# LQFP100_Breakout.net
KiCad netlist of a schematic drawn in EAGLE
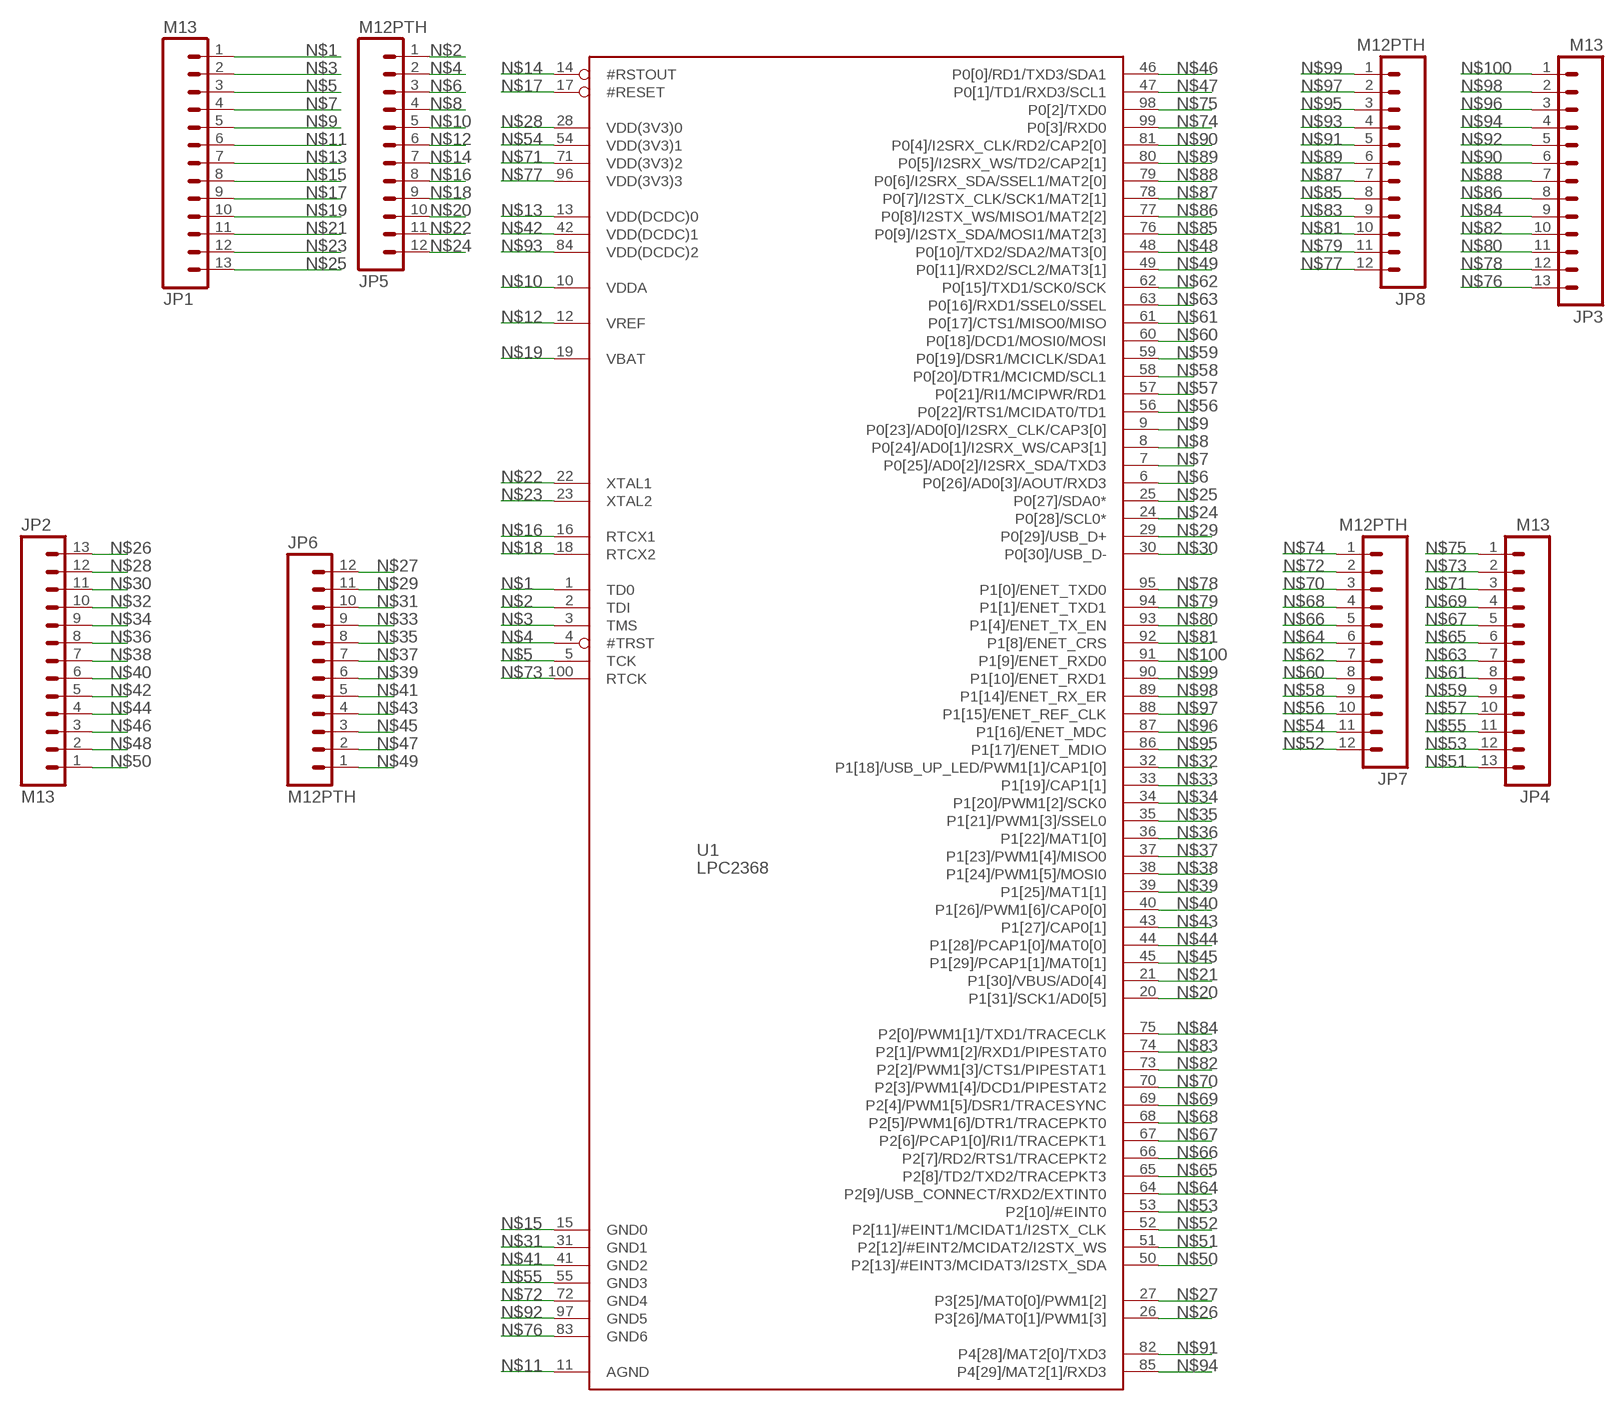
[diagram p0: schematic, sheet 1]

(export (version "E")
  (design (tool "Eeschema 10.0.6"))
  (components
    (comp (ref "JP1")
      (value "M13")
      (footprint "eagle-import:1X13")
      (libsource (lib "eagle-import") (part "M13"))
    )
    (comp (ref "JP2")
      (value "M13")
      (footprint "eagle-import:1X13")
      (libsource (lib "eagle-import") (part "M13"))
    )
    (comp (ref "JP3")
      (value "M13")
      (footprint "eagle-import:1X13")
      (libsource (lib "eagle-import") (part "M13"))
    )
    (comp (ref "JP4")
      (value "M13")
      (footprint "eagle-import:1X13")
      (libsource (lib "eagle-import") (part "M13"))
    )
    (comp (ref "JP5")
      (value "M12PTH")
      (footprint "eagle-import:1X12")
      (libsource (lib "eagle-import") (part "M12PTH"))
    )
    (comp (ref "JP6")
      (value "M12PTH")
      (footprint "eagle-import:1X12")
      (libsource (lib "eagle-import") (part "M12PTH"))
    )
    (comp (ref "JP7")
      (value "M12PTH")
      (footprint "eagle-import:1X12")
      (libsource (lib "eagle-import") (part "M12PTH"))
    )
    (comp (ref "JP8")
      (value "M12PTH")
      (footprint "eagle-import:1X12")
      (libsource (lib "eagle-import") (part "M12PTH"))
    )
    (comp (ref "U1")
      (value "LPC2368")
      (footprint "eagle-import:LQFP100")
      (libsource (lib "eagle-import") (part "LPC2368"))
    )
  )
  (nets
    (net (code "1") (name "/N$1") (class "Default")
      (node (ref "JP1") (pin "1") (pinfunction "1_1") (pintype "passive"))
      (node (ref "U1") (pin "1") (pinfunction "TD0_1") (pintype "bidirectional"))
    )
    (net (code "2") (name "/N$2") (class "Default")
      (node (ref "JP5") (pin "1") (pinfunction "1_1") (pintype "passive"))
      (node (ref "U1") (pin "2") (pinfunction "TDI_2") (pintype "bidirectional"))
    )
    (net (code "3") (name "/N$3") (class "Default")
      (node (ref "JP1") (pin "2") (pinfunction "2_2") (pintype "passive"))
      (node (ref "U1") (pin "3") (pinfunction "TMS_3") (pintype "bidirectional"))
    )
    (net (code "4") (name "/N$4") (class "Default")
      (node (ref "JP5") (pin "2") (pinfunction "2_2") (pintype "passive"))
      (node (ref "U1") (pin "4") (pinfunction "#TRST_4") (pintype "bidirectional"))
    )
    (net (code "5") (name "/N$5") (class "Default")
      (node (ref "JP1") (pin "3") (pinfunction "3_3") (pintype "passive"))
      (node (ref "U1") (pin "5") (pinfunction "TCK_5") (pintype "bidirectional"))
    )
    (net (code "6") (name "/N$6") (class "Default")
      (node (ref "JP5") (pin "3") (pinfunction "3_3") (pintype "passive"))
      (node (ref "U1") (pin "6") (pinfunction "P0[26]/AD0[3]/AOUT/RXD3_6") (pintype "bidirectional"))
    )
    (net (code "7") (name "/N$7") (class "Default")
      (node (ref "JP1") (pin "4") (pinfunction "4_4") (pintype "passive"))
      (node (ref "U1") (pin "7") (pinfunction "P0[25]/AD0[2]/I2SRX_SDA/TXD3_7") (pintype "bidirectional"))
    )
    (net (code "8") (name "/N$8") (class "Default")
      (node (ref "JP5") (pin "4") (pinfunction "4_4") (pintype "passive"))
      (node (ref "U1") (pin "8") (pinfunction "P0[24]/AD0[1]/I2SRX_WS/CAP3[1]_8") (pintype "bidirectional"))
    )
    (net (code "9") (name "/N$9") (class "Default")
      (node (ref "JP1") (pin "5") (pinfunction "5_5") (pintype "passive"))
      (node (ref "U1") (pin "9") (pinfunction "P0[23]/AD0[0]/I2SRX_CLK/CAP3[0]_9") (pintype "bidirectional"))
    )
    (net (code "10") (name "/N$10") (class "Default")
      (node (ref "JP5") (pin "5") (pinfunction "5_5") (pintype "passive"))
      (node (ref "U1") (pin "10") (pinfunction "VDDA_10") (pintype "bidirectional"))
    )
    (net (code "11") (name "/N$11") (class "Default")
      (node (ref "JP1") (pin "6") (pinfunction "6_6") (pintype "passive"))
      (node (ref "U1") (pin "11") (pinfunction "AGND_11") (pintype "bidirectional"))
    )
    (net (code "12") (name "/N$12") (class "Default")
      (node (ref "JP5") (pin "6") (pinfunction "6_6") (pintype "passive"))
      (node (ref "U1") (pin "12") (pinfunction "VREF_12") (pintype "bidirectional"))
    )
    (net (code "13") (name "/N$13") (class "Default")
      (node (ref "JP1") (pin "7") (pinfunction "7_7") (pintype "passive"))
      (node (ref "U1") (pin "13") (pinfunction "VDD(DCDC)0_13") (pintype "bidirectional"))
    )
    (net (code "14") (name "/N$14") (class "Default")
      (node (ref "JP5") (pin "7") (pinfunction "7_7") (pintype "passive"))
      (node (ref "U1") (pin "14") (pinfunction "#RSTOUT_14") (pintype "bidirectional"))
    )
    (net (code "15") (name "/N$15") (class "Default")
      (node (ref "JP1") (pin "8") (pinfunction "8_8") (pintype "passive"))
      (node (ref "U1") (pin "15") (pinfunction "GND0_15") (pintype "bidirectional"))
    )
    (net (code "16") (name "/N$16") (class "Default")
      (node (ref "JP5") (pin "8") (pinfunction "8_8") (pintype "passive"))
      (node (ref "U1") (pin "16") (pinfunction "RTCX1_16") (pintype "bidirectional"))
    )
    (net (code "17") (name "/N$17") (class "Default")
      (node (ref "JP1") (pin "9") (pinfunction "9_9") (pintype "passive"))
      (node (ref "U1") (pin "17") (pinfunction "#RESET_17") (pintype "bidirectional"))
    )
    (net (code "18") (name "/N$18") (class "Default")
      (node (ref "JP5") (pin "9") (pinfunction "9_9") (pintype "passive"))
      (node (ref "U1") (pin "18") (pinfunction "RTCX2_18") (pintype "bidirectional"))
    )
    (net (code "19") (name "/N$19") (class "Default")
      (node (ref "JP1") (pin "10") (pinfunction "10_10") (pintype "passive"))
      (node (ref "U1") (pin "19") (pinfunction "VBAT_19") (pintype "bidirectional"))
    )
    (net (code "20") (name "/N$20") (class "Default")
      (node (ref "JP5") (pin "10") (pinfunction "10_10") (pintype "passive"))
      (node (ref "U1") (pin "20") (pinfunction "P1[31]/SCK1/AD0[5]_20") (pintype "bidirectional"))
    )
    (net (code "21") (name "/N$21") (class "Default")
      (node (ref "JP1") (pin "11") (pinfunction "11_11") (pintype "passive"))
      (node (ref "U1") (pin "21") (pinfunction "P1[30]/VBUS/AD0[4]_21") (pintype "bidirectional"))
    )
    (net (code "22") (name "/N$22") (class "Default")
      (node (ref "JP5") (pin "11") (pinfunction "11_11") (pintype "passive"))
      (node (ref "U1") (pin "22") (pinfunction "XTAL1_22") (pintype "bidirectional"))
    )
    (net (code "23") (name "/N$23") (class "Default")
      (node (ref "JP1") (pin "12") (pinfunction "12_12") (pintype "passive"))
      (node (ref "U1") (pin "23") (pinfunction "XTAL2_23") (pintype "bidirectional"))
    )
    (net (code "24") (name "/N$24") (class "Default")
      (node (ref "JP5") (pin "12") (pinfunction "12_12") (pintype "passive"))
      (node (ref "U1") (pin "24") (pinfunction "P0[28]/SCL0*_24") (pintype "bidirectional"))
    )
    (net (code "25") (name "/N$25") (class "Default")
      (node (ref "JP1") (pin "13") (pinfunction "13_13") (pintype "passive"))
      (node (ref "U1") (pin "25") (pinfunction "P0[27]/SDA0*_25") (pintype "bidirectional"))
    )
    (net (code "26") (name "/N$26") (class "Default")
      (node (ref "JP2") (pin "13") (pinfunction "13_13") (pintype "passive"))
      (node (ref "U1") (pin "26") (pinfunction "P3[26]/MAT0[1]/PWM1[3]_26") (pintype "bidirectional"))
    )
    (net (code "27") (name "/N$27") (class "Default")
      (node (ref "JP6") (pin "12") (pinfunction "12_12") (pintype "passive"))
      (node (ref "U1") (pin "27") (pinfunction "P3[25]/MAT0[0]/PWM1[2]_27") (pintype "bidirectional"))
    )
    (net (code "28") (name "/N$28") (class "Default")
      (node (ref "JP2") (pin "12") (pinfunction "12_12") (pintype "passive"))
      (node (ref "U1") (pin "28") (pinfunction "VDD(3V3)0_28") (pintype "bidirectional"))
    )
    (net (code "29") (name "/N$29") (class "Default")
      (node (ref "JP6") (pin "11") (pinfunction "11_11") (pintype "passive"))
      (node (ref "U1") (pin "29") (pinfunction "P0[29]/USB_D+_29") (pintype "bidirectional"))
    )
    (net (code "30") (name "/N$30") (class "Default")
      (node (ref "JP2") (pin "11") (pinfunction "11_11") (pintype "passive"))
      (node (ref "U1") (pin "30") (pinfunction "P0[30]/USB_D-_30") (pintype "bidirectional"))
    )
    (net (code "31") (name "/N$31") (class "Default")
      (node (ref "JP6") (pin "10") (pinfunction "10_10") (pintype "passive"))
      (node (ref "U1") (pin "31") (pinfunction "GND1_31") (pintype "bidirectional"))
    )
    (net (code "32") (name "/N$32") (class "Default")
      (node (ref "JP2") (pin "10") (pinfunction "10_10") (pintype "passive"))
      (node (ref "U1") (pin "32") (pinfunction "P1[18]/USB_UP_LED/PWM1[1]/CAP1[0]_32") (pintype "bidirectional"))
    )
    (net (code "33") (name "/N$33") (class "Default")
      (node (ref "JP6") (pin "9") (pinfunction "9_9") (pintype "passive"))
      (node (ref "U1") (pin "33") (pinfunction "P1[19]/CAP1[1]_33") (pintype "bidirectional"))
    )
    (net (code "34") (name "/N$34") (class "Default")
      (node (ref "JP2") (pin "9") (pinfunction "9_9") (pintype "passive"))
      (node (ref "U1") (pin "34") (pinfunction "P1[20]/PWM1[2]/SCK0_34") (pintype "bidirectional"))
    )
    (net (code "35") (name "/N$35") (class "Default")
      (node (ref "JP6") (pin "8") (pinfunction "8_8") (pintype "passive"))
      (node (ref "U1") (pin "35") (pinfunction "P1[21]/PWM1[3]/SSEL0_35") (pintype "bidirectional"))
    )
    (net (code "36") (name "/N$36") (class "Default")
      (node (ref "JP2") (pin "8") (pinfunction "8_8") (pintype "passive"))
      (node (ref "U1") (pin "36") (pinfunction "P1[22]/MAT1[0]_36") (pintype "bidirectional"))
    )
    (net (code "37") (name "/N$37") (class "Default")
      (node (ref "JP6") (pin "7") (pinfunction "7_7") (pintype "passive"))
      (node (ref "U1") (pin "37") (pinfunction "P1[23]/PWM1[4]/MISO0_37") (pintype "bidirectional"))
    )
    (net (code "38") (name "/N$38") (class "Default")
      (node (ref "JP2") (pin "7") (pinfunction "7_7") (pintype "passive"))
      (node (ref "U1") (pin "38") (pinfunction "P1[24]/PWM1[5]/MOSI0_38") (pintype "bidirectional"))
    )
    (net (code "39") (name "/N$39") (class "Default")
      (node (ref "JP6") (pin "6") (pinfunction "6_6") (pintype "passive"))
      (node (ref "U1") (pin "39") (pinfunction "P1[25]/MAT1[1]_39") (pintype "bidirectional"))
    )
    (net (code "40") (name "/N$40") (class "Default")
      (node (ref "JP2") (pin "6") (pinfunction "6_6") (pintype "passive"))
      (node (ref "U1") (pin "40") (pinfunction "P1[26]/PWM1[6]/CAP0[0]_40") (pintype "bidirectional"))
    )
    (net (code "41") (name "/N$41") (class "Default")
      (node (ref "JP6") (pin "5") (pinfunction "5_5") (pintype "passive"))
      (node (ref "U1") (pin "41") (pinfunction "GND2_41") (pintype "bidirectional"))
    )
    (net (code "42") (name "/N$42") (class "Default")
      (node (ref "JP2") (pin "5") (pinfunction "5_5") (pintype "passive"))
      (node (ref "U1") (pin "42") (pinfunction "VDD(DCDC)1_42") (pintype "bidirectional"))
    )
    (net (code "43") (name "/N$43") (class "Default")
      (node (ref "JP6") (pin "4") (pinfunction "4_4") (pintype "passive"))
      (node (ref "U1") (pin "43") (pinfunction "P1[27]/CAP0[1]_43") (pintype "bidirectional"))
    )
    (net (code "44") (name "/N$44") (class "Default")
      (node (ref "JP2") (pin "4") (pinfunction "4_4") (pintype "passive"))
      (node (ref "U1") (pin "44") (pinfunction "P1[28]/PCAP1[0]/MAT0[0]_44") (pintype "bidirectional"))
    )
    (net (code "45") (name "/N$45") (class "Default")
      (node (ref "JP6") (pin "3") (pinfunction "3_3") (pintype "passive"))
      (node (ref "U1") (pin "45") (pinfunction "P1[29]/PCAP1[1]/MAT0[1]_45") (pintype "bidirectional"))
    )
    (net (code "46") (name "/N$46") (class "Default")
      (node (ref "JP2") (pin "3") (pinfunction "3_3") (pintype "passive"))
      (node (ref "U1") (pin "46") (pinfunction "P0[0]/RD1/TXD3/SDA1_46") (pintype "bidirectional"))
    )
    (net (code "47") (name "/N$47") (class "Default")
      (node (ref "JP6") (pin "2") (pinfunction "2_2") (pintype "passive"))
      (node (ref "U1") (pin "47") (pinfunction "P0[1]/TD1/RXD3/SCL1_47") (pintype "bidirectional"))
    )
    (net (code "48") (name "/N$48") (class "Default")
      (node (ref "JP2") (pin "2") (pinfunction "2_2") (pintype "passive"))
      (node (ref "U1") (pin "48") (pinfunction "P0[10]/TXD2/SDA2/MAT3[0]_48") (pintype "bidirectional"))
    )
    (net (code "49") (name "/N$49") (class "Default")
      (node (ref "JP6") (pin "1") (pinfunction "1_1") (pintype "passive"))
      (node (ref "U1") (pin "49") (pinfunction "P0[11]/RXD2/SCL2/MAT3[1]_49") (pintype "bidirectional"))
    )
    (net (code "50") (name "/N$50") (class "Default")
      (node (ref "JP2") (pin "1") (pinfunction "1_1") (pintype "passive"))
      (node (ref "U1") (pin "50") (pinfunction "P2[13]/#EINT3/MCIDAT3/I2STX_SDA_50") (pintype "bidirectional"))
    )
    (net (code "51") (name "/N$51") (class "Default")
      (node (ref "JP4") (pin "13") (pinfunction "13_13") (pintype "passive"))
      (node (ref "U1") (pin "51") (pinfunction "P2[12]/#EINT2/MCIDAT2/I2STX_WS_51") (pintype "bidirectional"))
    )
    (net (code "52") (name "/N$52") (class "Default")
      (node (ref "JP7") (pin "12") (pinfunction "12_12") (pintype "passive"))
      (node (ref "U1") (pin "52") (pinfunction "P2[11]/#EINT1/MCIDAT1/I2STX_CLK_52") (pintype "bidirectional"))
    )
    (net (code "53") (name "/N$53") (class "Default")
      (node (ref "JP4") (pin "12") (pinfunction "12_12") (pintype "passive"))
      (node (ref "U1") (pin "53") (pinfunction "P2[10]/#EINT0_53") (pintype "bidirectional"))
    )
    (net (code "54") (name "/N$54") (class "Default")
      (node (ref "JP7") (pin "11") (pinfunction "11_11") (pintype "passive"))
      (node (ref "U1") (pin "54") (pinfunction "VDD(3V3)1_54") (pintype "bidirectional"))
    )
    (net (code "55") (name "/N$55") (class "Default")
      (node (ref "JP4") (pin "11") (pinfunction "11_11") (pintype "passive"))
      (node (ref "U1") (pin "55") (pinfunction "GND3_55") (pintype "bidirectional"))
    )
    (net (code "56") (name "/N$56") (class "Default")
      (node (ref "JP7") (pin "10") (pinfunction "10_10") (pintype "passive"))
      (node (ref "U1") (pin "56") (pinfunction "P0[22]/RTS1/MCIDAT0/TD1_56") (pintype "bidirectional"))
    )
    (net (code "57") (name "/N$57") (class "Default")
      (node (ref "JP4") (pin "10") (pinfunction "10_10") (pintype "passive"))
      (node (ref "U1") (pin "57") (pinfunction "P0[21]/RI1/MCIPWR/RD1_57") (pintype "bidirectional"))
    )
    (net (code "58") (name "/N$58") (class "Default")
      (node (ref "JP7") (pin "9") (pinfunction "9_9") (pintype "passive"))
      (node (ref "U1") (pin "58") (pinfunction "P0[20]/DTR1/MCICMD/SCL1_58") (pintype "bidirectional"))
    )
    (net (code "59") (name "/N$59") (class "Default")
      (node (ref "JP4") (pin "9") (pinfunction "9_9") (pintype "passive"))
      (node (ref "U1") (pin "59") (pinfunction "P0[19]/DSR1/MCICLK/SDA1_59") (pintype "bidirectional"))
    )
    (net (code "60") (name "/N$60") (class "Default")
      (node (ref "JP7") (pin "8") (pinfunction "8_8") (pintype "passive"))
      (node (ref "U1") (pin "60") (pinfunction "P0[18]/DCD1/MOSI0/MOSI_60") (pintype "bidirectional"))
    )
    (net (code "61") (name "/N$61") (class "Default")
      (node (ref "JP4") (pin "8") (pinfunction "8_8") (pintype "passive"))
      (node (ref "U1") (pin "61") (pinfunction "P0[17]/CTS1/MISO0/MISO_61") (pintype "bidirectional"))
    )
    (net (code "62") (name "/N$62") (class "Default")
      (node (ref "JP7") (pin "7") (pinfunction "7_7") (pintype "passive"))
      (node (ref "U1") (pin "62") (pinfunction "P0[15]/TXD1/SCK0/SCK_62") (pintype "bidirectional"))
    )
    (net (code "63") (name "/N$63") (class "Default")
      (node (ref "JP4") (pin "7") (pinfunction "7_7") (pintype "passive"))
      (node (ref "U1") (pin "63") (pinfunction "P0[16]/RXD1/SSEL0/SSEL_63") (pintype "bidirectional"))
    )
    (net (code "64") (name "/N$64") (class "Default")
      (node (ref "JP7") (pin "6") (pinfunction "6_6") (pintype "passive"))
      (node (ref "U1") (pin "64") (pinfunction "P2[9]/USB_CONNECT/RXD2/EXTINT0_64") (pintype "bidirectional"))
    )
    (net (code "65") (name "/N$65") (class "Default")
      (node (ref "JP4") (pin "6") (pinfunction "6_6") (pintype "passive"))
      (node (ref "U1") (pin "65") (pinfunction "P2[8]/TD2/TXD2/TRACEPKT3_65") (pintype "bidirectional"))
    )
    (net (code "66") (name "/N$66") (class "Default")
      (node (ref "JP7") (pin "5") (pinfunction "5_5") (pintype "passive"))
      (node (ref "U1") (pin "66") (pinfunction "P2[7]/RD2/RTS1/TRACEPKT2_66") (pintype "bidirectional"))
    )
    (net (code "67") (name "/N$67") (class "Default")
      (node (ref "JP4") (pin "5") (pinfunction "5_5") (pintype "passive"))
      (node (ref "U1") (pin "67") (pinfunction "P2[6]/PCAP1[0]/RI1/TRACEPKT1_67") (pintype "bidirectional"))
    )
    (net (code "68") (name "/N$68") (class "Default")
      (node (ref "JP7") (pin "4") (pinfunction "4_4") (pintype "passive"))
      (node (ref "U1") (pin "68") (pinfunction "P2[5]/PWM1[6]/DTR1/TRACEPKT0_68") (pintype "bidirectional"))
    )
    (net (code "69") (name "/N$69") (class "Default")
      (node (ref "JP4") (pin "4") (pinfunction "4_4") (pintype "passive"))
      (node (ref "U1") (pin "69") (pinfunction "P2[4]/PWM1[5]/DSR1/TRACESYNC_69") (pintype "bidirectional"))
    )
    (net (code "70") (name "/N$70") (class "Default")
      (node (ref "JP7") (pin "3") (pinfunction "3_3") (pintype "passive"))
      (node (ref "U1") (pin "70") (pinfunction "P2[3]/PWM1[4]/DCD1/PIPESTAT2_70") (pintype "bidirectional"))
    )
    (net (code "71") (name "/N$71") (class "Default")
      (node (ref "JP4") (pin "3") (pinfunction "3_3") (pintype "passive"))
      (node (ref "U1") (pin "71") (pinfunction "VDD(3V3)2_71") (pintype "bidirectional"))
    )
    (net (code "72") (name "/N$72") (class "Default")
      (node (ref "JP7") (pin "2") (pinfunction "2_2") (pintype "passive"))
      (node (ref "U1") (pin "72") (pinfunction "GND4_72") (pintype "bidirectional"))
    )
    (net (code "73") (name "/N$73") (class "Default")
      (node (ref "JP4") (pin "2") (pinfunction "2_2") (pintype "passive"))
      (node (ref "U1") (pin "100") (pinfunction "RTCK_100") (pintype "bidirectional"))
    )
    (net (code "74") (name "/N$74") (class "Default")
      (node (ref "JP7") (pin "1") (pinfunction "1_1") (pintype "passive"))
      (node (ref "U1") (pin "99") (pinfunction "P0[3]/RXD0_99") (pintype "bidirectional"))
    )
    (net (code "75") (name "/N$75") (class "Default")
      (node (ref "JP4") (pin "1") (pinfunction "1_1") (pintype "passive"))
      (node (ref "U1") (pin "98") (pinfunction "P0[2]/TXD0_98") (pintype "bidirectional"))
    )
    (net (code "76") (name "/N$76") (class "Default")
      (node (ref "JP3") (pin "13") (pinfunction "13_13") (pintype "passive"))
      (node (ref "U1") (pin "83") (pinfunction "GND6_83") (pintype "bidirectional"))
    )
    (net (code "77") (name "/N$77") (class "Default")
      (node (ref "JP8") (pin "12") (pinfunction "12_12") (pintype "passive"))
      (node (ref "U1") (pin "96") (pinfunction "VDD(3V3)3_96") (pintype "bidirectional"))
    )
    (net (code "78") (name "/N$78") (class "Default")
      (node (ref "JP3") (pin "12") (pinfunction "12_12") (pintype "passive"))
      (node (ref "U1") (pin "95") (pinfunction "P1[0]/ENET_TXD0_95") (pintype "bidirectional"))
    )
    (net (code "79") (name "/N$79") (class "Default")
      (node (ref "JP8") (pin "11") (pinfunction "11_11") (pintype "passive"))
      (node (ref "U1") (pin "94") (pinfunction "P1[1]/ENET_TXD1_94") (pintype "bidirectional"))
    )
    (net (code "80") (name "/N$80") (class "Default")
      (node (ref "JP3") (pin "11") (pinfunction "11_11") (pintype "passive"))
      (node (ref "U1") (pin "93") (pinfunction "P1[4]/ENET_TX_EN_93") (pintype "bidirectional"))
    )
    (net (code "81") (name "/N$81") (class "Default")
      (node (ref "JP8") (pin "10") (pinfunction "10_10") (pintype "passive"))
      (node (ref "U1") (pin "92") (pinfunction "P1[8]/ENET_CRS_92") (pintype "bidirectional"))
    )
    (net (code "82") (name "/N$82") (class "Default")
      (node (ref "JP3") (pin "10") (pinfunction "10_10") (pintype "passive"))
      (node (ref "U1") (pin "73") (pinfunction "P2[2]/PWM1[3]/CTS1/PIPESTAT1_73") (pintype "bidirectional"))
    )
    (net (code "83") (name "/N$83") (class "Default")
      (node (ref "JP8") (pin "9") (pinfunction "9_9") (pintype "passive"))
      (node (ref "U1") (pin "74") (pinfunction "P2[1]/PWM1[2]/RXD1/PIPESTAT0_74") (pintype "bidirectional"))
    )
    (net (code "84") (name "/N$84") (class "Default")
      (node (ref "JP3") (pin "9") (pinfunction "9_9") (pintype "passive"))
      (node (ref "U1") (pin "75") (pinfunction "P2[0]/PWM1[1]/TXD1/TRACECLK_75") (pintype "bidirectional"))
    )
    (net (code "85") (name "/N$85") (class "Default")
      (node (ref "JP8") (pin "8") (pinfunction "8_8") (pintype "passive"))
      (node (ref "U1") (pin "76") (pinfunction "P0[9]/I2STX_SDA/MOSI1/MAT2[3]_76") (pintype "bidirectional"))
    )
    (net (code "86") (name "/N$86") (class "Default")
      (node (ref "JP3") (pin "8") (pinfunction "8_8") (pintype "passive"))
      (node (ref "U1") (pin "77") (pinfunction "P0[8]/I2STX_WS/MISO1/MAT2[2]_77") (pintype "bidirectional"))
    )
    (net (code "87") (name "/N$87") (class "Default")
      (node (ref "JP8") (pin "7") (pinfunction "7_7") (pintype "passive"))
      (node (ref "U1") (pin "78") (pinfunction "P0[7]/I2STX_CLK/SCK1/MAT2[1]_78") (pintype "bidirectional"))
    )
    (net (code "88") (name "/N$88") (class "Default")
      (node (ref "JP3") (pin "7") (pinfunction "7_7") (pintype "passive"))
      (node (ref "U1") (pin "79") (pinfunction "P0[6]/I2SRX_SDA/SSEL1/MAT2[0]_79") (pintype "bidirectional"))
    )
    (net (code "89") (name "/N$89") (class "Default")
      (node (ref "JP8") (pin "6") (pinfunction "6_6") (pintype "passive"))
      (node (ref "U1") (pin "80") (pinfunction "P0[5]/I2SRX_WS/TD2/CAP2[1]_80") (pintype "bidirectional"))
    )
    (net (code "90") (name "/N$90") (class "Default")
      (node (ref "JP3") (pin "6") (pinfunction "6_6") (pintype "passive"))
      (node (ref "U1") (pin "81") (pinfunction "P0[4]/I2SRX_CLK/RD2/CAP2[0]_81") (pintype "bidirectional"))
    )
    (net (code "91") (name "/N$91") (class "Default")
      (node (ref "JP8") (pin "5") (pinfunction "5_5") (pintype "passive"))
      (node (ref "U1") (pin "82") (pinfunction "P4[28]/MAT2[0]/TXD3_82") (pintype "bidirectional"))
    )
    (net (code "92") (name "/N$92") (class "Default")
      (node (ref "JP3") (pin "5") (pinfunction "5_5") (pintype "passive"))
      (node (ref "U1") (pin "97") (pinfunction "GND5_97") (pintype "bidirectional"))
    )
    (net (code "93") (name "/N$93") (class "Default")
      (node (ref "JP8") (pin "4") (pinfunction "4_4") (pintype "passive"))
      (node (ref "U1") (pin "84") (pinfunction "VDD(DCDC)2_84") (pintype "bidirectional"))
    )
    (net (code "94") (name "/N$94") (class "Default")
      (node (ref "JP3") (pin "4") (pinfunction "4_4") (pintype "passive"))
      (node (ref "U1") (pin "85") (pinfunction "P4[29]/MAT2[1]/RXD3_85") (pintype "bidirectional"))
    )
    (net (code "95") (name "/N$95") (class "Default")
      (node (ref "JP8") (pin "3") (pinfunction "3_3") (pintype "passive"))
      (node (ref "U1") (pin "86") (pinfunction "P1[17]/ENET_MDIO_86") (pintype "bidirectional"))
    )
    (net (code "96") (name "/N$96") (class "Default")
      (node (ref "JP3") (pin "3") (pinfunction "3_3") (pintype "passive"))
      (node (ref "U1") (pin "87") (pinfunction "P1[16]/ENET_MDC_87") (pintype "bidirectional"))
    )
    (net (code "97") (name "/N$97") (class "Default")
      (node (ref "JP8") (pin "2") (pinfunction "2_2") (pintype "passive"))
      (node (ref "U1") (pin "88") (pinfunction "P1[15]/ENET_REF_CLK_88") (pintype "bidirectional"))
    )
    (net (code "98") (name "/N$98") (class "Default")
      (node (ref "JP3") (pin "2") (pinfunction "2_2") (pintype "passive"))
      (node (ref "U1") (pin "89") (pinfunction "P1[14]/ENET_RX_ER_89") (pintype "bidirectional"))
    )
    (net (code "99") (name "/N$99") (class "Default")
      (node (ref "JP8") (pin "1") (pinfunction "1_1") (pintype "passive"))
      (node (ref "U1") (pin "90") (pinfunction "P1[10]/ENET_RXD1_90") (pintype "bidirectional"))
    )
    (net (code "100") (name "/N$100") (class "Default")
      (node (ref "JP3") (pin "1") (pinfunction "1_1") (pintype "passive"))
      (node (ref "U1") (pin "91") (pinfunction "P1[9]/ENET_RXD0_91") (pintype "bidirectional"))
    )
  )
)
